# core_module.net
KiCad netlist of a schematic drawn in Altium Designer
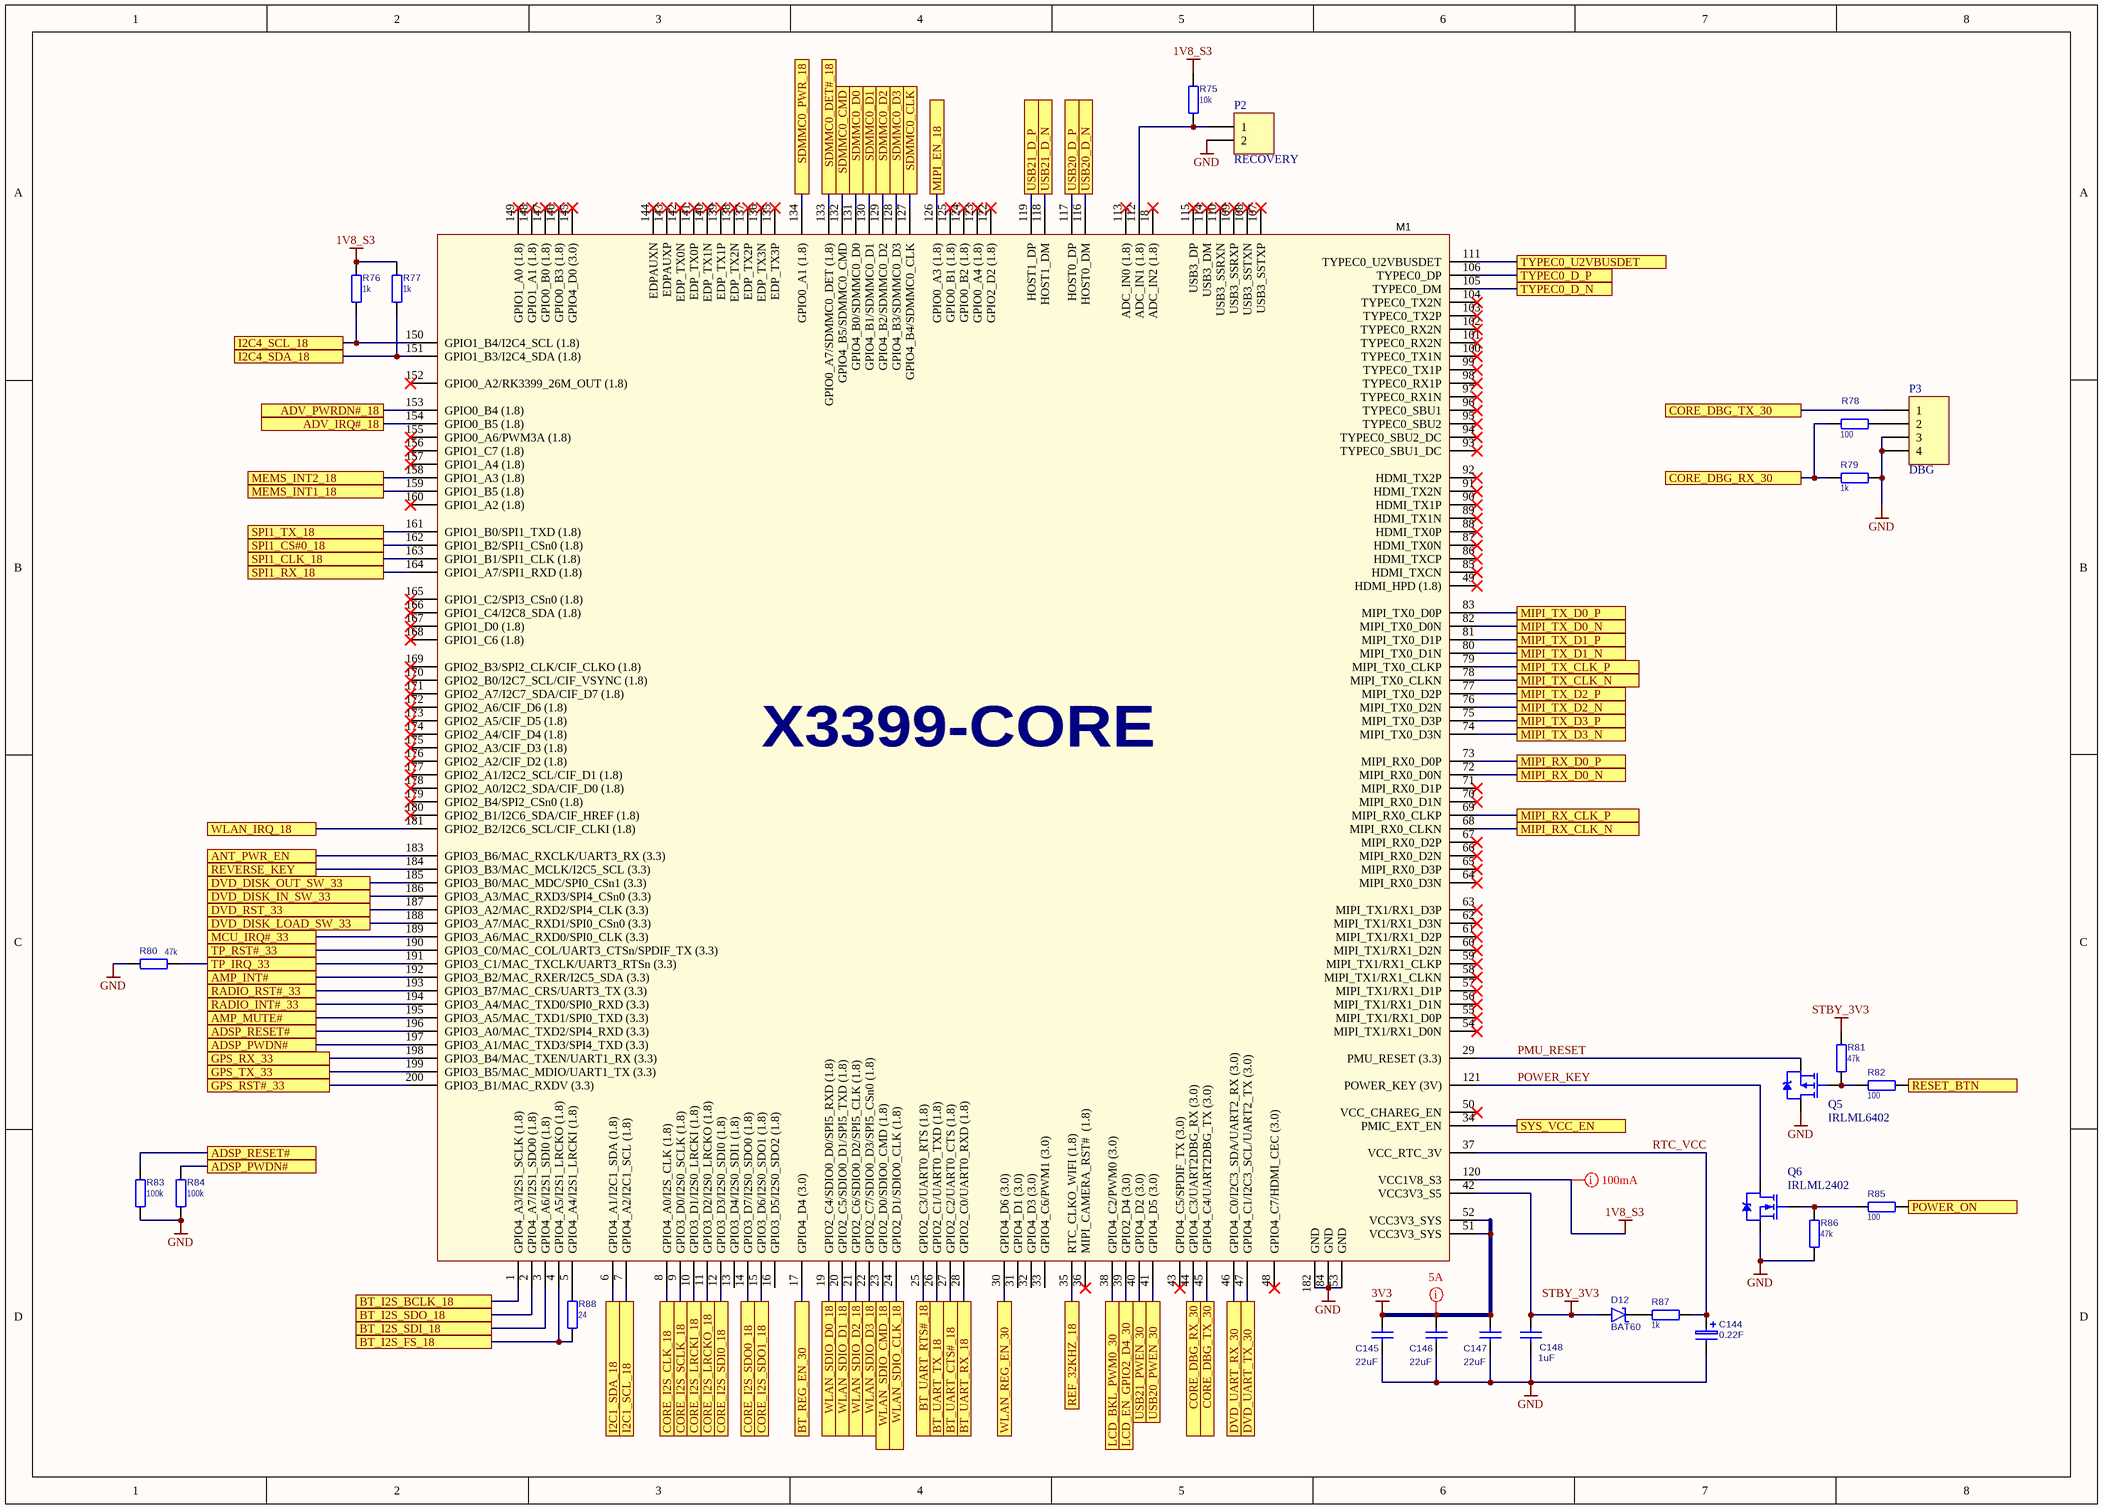
[diagram p0: core_module.SchDoc]

(export (version "E")
  (design (tool "Eeschema 10.0.6"))
  (components
    (comp (ref "C144")
      (value "0.22F")
      (footprint "Capacitors:DS/DSK")
      (description "CAP_POL")
      (libsource (lib "capacitors") (part "CAP_POL"))
    )
    (comp (ref "C145")
      (value "22uF")
      (footprint "Capacitors:C0805")
      (description "CAP_NPOL")
      (fields (field (name "Comment") "CL21A226MQQNNNE"))
      (libsource (lib "capacitors") (part "CAP_NPOL"))
    )
    (comp (ref "C146")
      (value "22uF")
      (footprint "Capacitors:C0805")
      (description "CAP_NPOL")
      (fields (field (name "Comment") "CL21A226MQQNNNE"))
      (libsource (lib "capacitors") (part "CAP_NPOL"))
    )
    (comp (ref "C147")
      (value "22uF")
      (footprint "Capacitors:C0805")
      (description "CAP_NPOL")
      (fields (field (name "Comment") "CL21A226MQQNNNE"))
      (libsource (lib "capacitors") (part "CAP_NPOL"))
    )
    (comp (ref "C148")
      (value "1uF")
      (footprint "Capacitors:C0603")
      (description "CAP_NPOL")
      (fields (field (name "Comment") "CC0603KRX7R9BB105"))
      (libsource (lib "capacitors") (part "CAP_NPOL"))
    )
    (comp (ref "D12")
      (value "BAT60")
      (footprint "SOD-323")
      (description "SHOTTKY")
      (fields (field (name "Comment") "BAT60AE6327HTSA1"))
      (libsource (lib "diodes") (part "SHOTTKY"))
    )
    (comp (ref "M1")
      (value "X3399-CORE")
      (footprint "X3399-CORE")
      (description "RK3399 Six-Core 64-bit")
      (libsource (lib "X3399-CORE") (part "X3399-CORE"))
    )
    (comp (ref "P2")
      (value "RECOVERY")
      (footprint "HDR:PLS-2")
      (description "Header, 2-Pin")
      (fields (field (name "PUBLISHER") "Altium Limited"))
      (libsource (lib "HDR") (part "HDR 2"))
    )
    (comp (ref "P3")
      (value "DBG")
      (footprint "PLD-2")
      (description "Header, 4-Pin")
      (fields (field (name "PUBLISHER") "Altium Limited"))
      (libsource (lib "HDR") (part "HDR 4"))
    )
    (comp (ref "Q5")
      (value "IRLML6402")
      (footprint "SOT:SOT-23-3")
      (description "HEXFET Power MOSFET")
      (libsource (lib "MOSFET") (part "P-Channel"))
    )
    (comp (ref "Q6")
      (value "IRLML2402")
      (footprint "SOT:SOT-23-3")
      (description "HEXFET Power MOSFET")
      (libsource (lib "MOSFET") (part "N-Channel"))
    )
    (comp (ref "R75")
      (value "10k")
      (footprint "R0603")
      (description "RES")
      (libsource (lib "resistors") (part "RESISTOR"))
    )
    (comp (ref "R76")
      (value "1k")
      (footprint "R0603")
      (description "RES")
      (libsource (lib "resistors") (part "RESISTOR"))
    )
    (comp (ref "R77")
      (value "1k")
      (footprint "R0603")
      (description "RES")
      (libsource (lib "resistors") (part "RESISTOR"))
    )
    (comp (ref "R78")
      (value "100")
      (footprint "R0603")
      (description "RES")
      (libsource (lib "resistors") (part "RESISTOR"))
    )
    (comp (ref "R79")
      (value "1k")
      (footprint "R0603")
      (description "RES")
      (libsource (lib "resistors") (part "RESISTOR"))
    )
    (comp (ref "R80")
      (value "47k")
      (footprint "R0603")
      (description "RES")
      (libsource (lib "resistors") (part "RESISTOR"))
    )
    (comp (ref "R81")
      (value "47k")
      (footprint "R0603")
      (description "RES")
      (libsource (lib "resistors") (part "RESISTOR"))
    )
    (comp (ref "R82")
      (value "100")
      (footprint "R0603")
      (description "RES")
      (libsource (lib "resistors") (part "RESISTOR"))
    )
    (comp (ref "R83")
      (value "100k")
      (footprint "R0603")
      (description "RES")
      (libsource (lib "resistors") (part "RESISTOR"))
    )
    (comp (ref "R84")
      (value "100k")
      (footprint "R0603")
      (description "RES")
      (libsource (lib "resistors") (part "RESISTOR"))
    )
    (comp (ref "R85")
      (value "100")
      (footprint "R0603")
      (description "RES")
      (libsource (lib "resistors") (part "RESISTOR"))
    )
    (comp (ref "R86")
      (value "47k")
      (footprint "R0603")
      (description "RES")
      (libsource (lib "resistors") (part "RESISTOR"))
    )
    (comp (ref "R87")
      (value "1k")
      (footprint "R0603")
      (description "RES")
      (libsource (lib "resistors") (part "RESISTOR"))
    )
    (comp (ref "R88")
      (value "24")
      (footprint "R0603")
      (description "RES")
      (libsource (lib "resistors") (part "RESISTOR"))
    )
  )
  (nets
    (net (code "1") (name "/ADSP_PWDN#") (class "Default")
      (node (ref "M1") (pin "197") (pinfunction "GPIO3_A1/MAC_TXD3/SPI4_TXD_(3.3)_197") (pintype "passive"))
      (node (ref "R84") (pin "1") (pinfunction "1_1") (pintype "passive"))
    )
    (net (code "2") (name "/ADSP_RESET#") (class "Default")
      (node (ref "M1") (pin "196") (pinfunction "GPIO3_A0/MAC_TXD2/SPI4_RXD_(3.3)_196") (pintype "passive"))
      (node (ref "R83") (pin "1") (pinfunction "1_1") (pintype "passive"))
    )
    (net (code "3") (name "/ADV_IRQ#_18") (class "Default")
      (node (ref "M1") (pin "154") (pinfunction "GPIO0_B5_(1.8)_154") (pintype "passive"))
    )
    (net (code "4") (name "/ADV_PWRDN#_18") (class "Default")
      (node (ref "M1") (pin "153") (pinfunction "GPIO0_B4_(1.8)_153") (pintype "passive"))
    )
    (net (code "5") (name "/AMP_INT#") (class "Default")
      (node (ref "M1") (pin "192") (pinfunction "GPIO3_B2/MAC_RXER/I2C5_SDA_(3.3)_192") (pintype "passive"))
    )
    (net (code "6") (name "/AMP_MUTE#") (class "Default")
      (node (ref "M1") (pin "195") (pinfunction "GPIO3_A5/MAC_TXD1/SPI0_TXD_(3.3)_195") (pintype "passive"))
    )
    (net (code "7") (name "/ANT_PWR_EN") (class "Default")
      (node (ref "M1") (pin "183") (pinfunction "GPIO3_B6/MAC_RXCLK/UART3_RX_(3.3)_183") (pintype "passive"))
    )
    (net (code "8") (name "/BT_I2S_BCLK_18") (class "Default")
      (node (ref "M1") (pin "1") (pinfunction "GPIO4_A3/I2S1_SCLK_(1.8)_1") (pintype "passive"))
    )
    (net (code "9") (name "/BT_I2S_FS_18") (class "Default")
      (node (ref "M1") (pin "4") (pinfunction "GPIO4_A5/I2S1_LRCKO_(1.8)_4") (pintype "passive"))
      (node (ref "R88") (pin "2") (pinfunction "2_2") (pintype "passive"))
    )
    (net (code "10") (name "/BT_I2S_SDI_18") (class "Default")
      (node (ref "M1") (pin "3") (pinfunction "GPIO4_A6/I2S1_SDI0_(1.8)_3") (pintype "passive"))
    )
    (net (code "11") (name "/BT_I2S_SDO_18") (class "Default")
      (node (ref "M1") (pin "2") (pinfunction "GPIO4_A7/I2S1_SDO0_(1.8)_2") (pintype "passive"))
    )
    (net (code "12") (name "/BT_REG_EN_30") (class "Default")
      (node (ref "M1") (pin "17") (pinfunction "GPIO4_D4_(3.0)_17") (pintype "passive"))
    )
    (net (code "13") (name "/BT_UART_CTS#_18") (class "Default")
      (node (ref "M1") (pin "27") (pinfunction "GPIO2_C2/UART0_CTS_(1.8)_27") (pintype "passive"))
    )
    (net (code "14") (name "/BT_UART_RTS#_18") (class "Default")
      (node (ref "M1") (pin "25") (pinfunction "GPIO2_C3/UART0_RTS_(1.8)_25") (pintype "passive"))
    )
    (net (code "15") (name "/BT_UART_RX_18") (class "Default")
      (node (ref "M1") (pin "28") (pinfunction "GPIO2_C0/UART0_RXD_(1.8)_28") (pintype "passive"))
    )
    (net (code "16") (name "/BT_UART_TX_18") (class "Default")
      (node (ref "M1") (pin "26") (pinfunction "GPIO2_C1/UART0_TXD_(1.8)_26") (pintype "passive"))
    )
    (net (code "17") (name "/CORE_DBG_RX_30") (class "Default")
      (node (ref "M1") (pin "44") (pinfunction "GPIO4_C3/UART2DBG_RX_(3.0)_44") (pintype "passive"))
      (node (ref "R78") (pin "2") (pinfunction "2_2") (pintype "passive"))
      (node (ref "R79") (pin "1") (pinfunction "1_1") (pintype "passive"))
    )
    (net (code "18") (name "/CORE_DBG_TX_30") (class "Default")
      (node (ref "M1") (pin "45") (pinfunction "GPIO4_C4/UART2DBG_TX_(3.0)_45") (pintype "passive"))
      (node (ref "P3") (pin "1") (pinfunction "1_1") (pintype "passive"))
    )
    (net (code "19") (name "/CORE_I2S_CLK_18") (class "Default")
      (node (ref "M1") (pin "8") (pinfunction "GPIO4_A0/I2S_CLK_(1.8)_8") (pintype "passive"))
    )
    (net (code "20") (name "/CORE_I2S_LRCKI_18") (class "Default")
      (node (ref "M1") (pin "10") (pinfunction "GPIO3_D1/I2S0_LRCKI_(1.8)_10") (pintype "passive"))
    )
    (net (code "21") (name "/CORE_I2S_LRCKO_18") (class "Default")
      (node (ref "M1") (pin "11") (pinfunction "GPIO3_D2/I2S0_LRCKO_(1.8)_11") (pintype "passive"))
    )
    (net (code "22") (name "/CORE_I2S_SCLK_18") (class "Default")
      (node (ref "M1") (pin "9") (pinfunction "GPIO3_D0/I2S0_SCLK_(1.8)_9") (pintype "passive"))
    )
    (net (code "23") (name "/CORE_I2S_SDI0_18") (class "Default")
      (node (ref "M1") (pin "12") (pinfunction "GPIO3_D3/I2S0_SDI0_(1.8)_12") (pintype "passive"))
    )
    (net (code "24") (name "/CORE_I2S_SDO0_18") (class "Default")
      (node (ref "M1") (pin "14") (pinfunction "GPIO3_D7/I2S0_SDO0_(1.8)_14") (pintype "passive"))
    )
    (net (code "25") (name "/CORE_I2S_SDO1_18") (class "Default")
      (node (ref "M1") (pin "15") (pinfunction "GPIO3_D6/I2S0_SDO1_(1.8)_15") (pintype "passive"))
    )
    (net (code "26") (name "/DVD_DISK_IN_SW_33") (class "Default")
      (node (ref "M1") (pin "186") (pinfunction "GPIO3_A3/MAC_RXD3/SPI4_CSn0_(3.3)_186") (pintype "passive"))
    )
    (net (code "27") (name "/DVD_DISK_LOAD_SW_33") (class "Default")
      (node (ref "M1") (pin "188") (pinfunction "GPIO3_A7/MAC_RXD1/SPI0_CSn0_(3.3)_188") (pintype "passive"))
    )
    (net (code "28") (name "/DVD_DISK_OUT_SW_33") (class "Default")
      (node (ref "M1") (pin "185") (pinfunction "GPIO3_B0/MAC_MDC/SPI0_CSn1_(3.3)_185") (pintype "passive"))
    )
    (net (code "29") (name "/DVD_RST_33") (class "Default")
      (node (ref "M1") (pin "187") (pinfunction "GPIO3_A2/MAC_RXD2/SPI4_CLK_(3.3)_187") (pintype "passive"))
    )
    (net (code "30") (name "/DVD_UART_RX_30") (class "Default")
      (node (ref "M1") (pin "46") (pinfunction "GPIO4_C0/I2C3_SDA/UART2_RX_(3.0)_46") (pintype "passive"))
    )
    (net (code "31") (name "/DVD_UART_TX_30") (class "Default")
      (node (ref "M1") (pin "47") (pinfunction "GPIO4_C1/I2C3_SCL/UART2_TX_(3.0)_47") (pintype "passive"))
    )
    (net (code "32") (name "/GPS_RST#_33") (class "Default")
      (node (ref "M1") (pin "200") (pinfunction "GPIO3_B1/MAC_RXDV_(3.3)_200") (pintype "passive"))
    )
    (net (code "33") (name "/GPS_RX_33") (class "Default")
      (node (ref "M1") (pin "198") (pinfunction "GPIO3_B4/MAC_TXEN/UART1_RX_(3.3)_198") (pintype "passive"))
    )
    (net (code "34") (name "/GPS_TX_33") (class "Default")
      (node (ref "M1") (pin "199") (pinfunction "GPIO3_B5/MAC_MDIO/UART1_TX_(3.3)_199") (pintype "passive"))
    )
    (net (code "35") (name "/I2C1_SCL_18") (class "Default")
      (node (ref "M1") (pin "7") (pinfunction "GPIO4_A2/I2C1_SCL_(1.8)_7") (pintype "passive"))
    )
    (net (code "36") (name "/I2C1_SDA_18") (class "Default")
      (node (ref "M1") (pin "6") (pinfunction "GPIO4_A1/I2C1_SDA_(1.8)_6") (pintype "passive"))
    )
    (net (code "37") (name "/I2C4_SCL_18") (class "Default")
      (node (ref "M1") (pin "150") (pinfunction "GPIO1_B4/I2C4_SCL_(1.8)_150") (pintype "passive"))
      (node (ref "R76") (pin "1") (pinfunction "1_1") (pintype "passive"))
    )
    (net (code "38") (name "/I2C4_SDA_18") (class "Default")
      (node (ref "M1") (pin "151") (pinfunction "GPIO1_B3/I2C4_SDA_(1.8)_151") (pintype "passive"))
      (node (ref "R77") (pin "2") (pinfunction "2_2") (pintype "passive"))
    )
    (net (code "39") (name "/LCD_BKL_PWM0_30") (class "Default")
      (node (ref "M1") (pin "38") (pinfunction "GPIO4_C2/PWM0_(3.0)_38") (pintype "passive"))
    )
    (net (code "40") (name "/LCD_EN_GPIO2_D4_30") (class "Default")
      (node (ref "M1") (pin "39") (pinfunction "GPIO2_D4_(3.0)_39") (pintype "passive"))
    )
    (net (code "41") (name "/MCU_IRQ#_33") (class "Default")
      (node (ref "M1") (pin "189") (pinfunction "GPIO3_A6/MAC_RXD0/SPI0_CLK_(3.3)_189") (pintype "passive"))
    )
    (net (code "42") (name "/MEMS_INT1_18") (class "Default")
      (node (ref "M1") (pin "159") (pinfunction "GPIO1_B5_(1.8)_159") (pintype "passive"))
    )
    (net (code "43") (name "/MEMS_INT2_18") (class "Default")
      (node (ref "M1") (pin "158") (pinfunction "GPIO1_A3_(1.8)_158") (pintype "passive"))
    )
    (net (code "44") (name "/MIPI_EN_18") (class "Default")
      (node (ref "M1") (pin "126") (pinfunction "GPIO0_A3_(1.8)_126") (pintype "passive"))
    )
    (net (code "45") (name "/MIPI_RX_CLK_N") (class "Default")
      (node (ref "M1") (pin "68") (pinfunction "MIPI_RX0_CLKN_68") (pintype "passive"))
    )
    (net (code "46") (name "/MIPI_RX_CLK_P") (class "Default")
      (node (ref "M1") (pin "69") (pinfunction "MIPI_RX0_CLKP_69") (pintype "passive"))
    )
    (net (code "47") (name "/MIPI_RX_D0_N") (class "Default")
      (node (ref "M1") (pin "72") (pinfunction "MIPI_RX0_D0N_72") (pintype "passive"))
    )
    (net (code "48") (name "/MIPI_RX_D0_P") (class "Default")
      (node (ref "M1") (pin "73") (pinfunction "MIPI_RX0_D0P_73") (pintype "passive"))
    )
    (net (code "49") (name "/MIPI_TX_CLK_N") (class "Default")
      (node (ref "M1") (pin "78") (pinfunction "MIPI_TX0_CLKN_78") (pintype "passive"))
    )
    (net (code "50") (name "/MIPI_TX_CLK_P") (class "Default")
      (node (ref "M1") (pin "79") (pinfunction "MIPI_TX0_CLKP_79") (pintype "passive"))
    )
    (net (code "51") (name "/MIPI_TX_D0_N") (class "Default")
      (node (ref "M1") (pin "82") (pinfunction "MIPI_TX0_D0N_82") (pintype "passive"))
    )
    (net (code "52") (name "/MIPI_TX_D0_P") (class "Default")
      (node (ref "M1") (pin "83") (pinfunction "MIPI_TX0_D0P_83") (pintype "passive"))
    )
    (net (code "53") (name "/MIPI_TX_D1_N") (class "Default")
      (node (ref "M1") (pin "80") (pinfunction "MIPI_TX0_D1N_80") (pintype "passive"))
    )
    (net (code "54") (name "/MIPI_TX_D1_P") (class "Default")
      (node (ref "M1") (pin "81") (pinfunction "MIPI_TX0_D1P_81") (pintype "passive"))
    )
    (net (code "55") (name "/MIPI_TX_D2_N") (class "Default")
      (node (ref "M1") (pin "76") (pinfunction "MIPI_TX0_D2N_76") (pintype "passive"))
    )
    (net (code "56") (name "/MIPI_TX_D2_P") (class "Default")
      (node (ref "M1") (pin "77") (pinfunction "MIPI_TX0_D2P_77") (pintype "passive"))
    )
    (net (code "57") (name "/MIPI_TX_D3_N") (class "Default")
      (node (ref "M1") (pin "74") (pinfunction "MIPI_TX0_D3N_74") (pintype "passive"))
    )
    (net (code "58") (name "/MIPI_TX_D3_P") (class "Default")
      (node (ref "M1") (pin "75") (pinfunction "MIPI_TX0_D3P_75") (pintype "passive"))
    )
    (net (code "59") (name "/PMU_RESET") (class "Default")
      (node (ref "M1") (pin "29") (pinfunction "PMU_RESET_(3.3)_29") (pintype "passive"))
      (node (ref "Q5") (pin "2") (pinfunction "S_2") (pintype "passive"))
    )
    (net (code "60") (name "/POWER_KEY") (class "Default")
      (node (ref "M1") (pin "121") (pinfunction "POWER_KEY_(3V)_121") (pintype "passive"))
      (node (ref "Q6") (pin "3") (pinfunction "D_3") (pintype "passive"))
    )
    (net (code "61") (name "/POWER_ON") (class "Default")
      (node (ref "R85") (pin "1") (pinfunction "1_1") (pintype "passive"))
    )
    (net (code "62") (name "/RADIO_INT#_33") (class "Default")
      (node (ref "M1") (pin "194") (pinfunction "GPIO3_A4/MAC_TXD0/SPI0_RXD_(3.3)_194") (pintype "passive"))
    )
    (net (code "63") (name "/RADIO_RST#_33") (class "Default")
      (node (ref "M1") (pin "193") (pinfunction "GPIO3_B7/MAC_CRS/UART3_TX_(3.3)_193") (pintype "passive"))
    )
    (net (code "64") (name "/REF_32KHZ_18") (class "Default")
      (node (ref "M1") (pin "35") (pinfunction "RTC_CLKO_WIFI_(1.8)_35") (pintype "passive"))
    )
    (net (code "65") (name "/RESET_BTN") (class "Default")
      (node (ref "R82") (pin "1") (pinfunction "1_1") (pintype "passive"))
    )
    (net (code "66") (name "/REVERSE_KEY") (class "Default")
      (node (ref "M1") (pin "184") (pinfunction "GPIO3_B3/MAC_MCLK/I2C5_SCL_(3.3)_184") (pintype "passive"))
    )
    (net (code "67") (name "/RTC_VCC") (class "Default")
      (node (ref "C144") (pin "1") (pinfunction "+_1") (pintype "passive"))
      (node (ref "M1") (pin "37") (pinfunction "VCC_RTC_3V_37") (pintype "passive"))
      (node (ref "R87") (pin "1") (pinfunction "1_1") (pintype "passive"))
    )
    (net (code "68") (name "/SDMMC0_CLK") (class "Default")
      (node (ref "M1") (pin "127") (pinfunction "GPIO4_B4/SDMMC0_CLK_127") (pintype "passive"))
    )
    (net (code "69") (name "/SDMMC0_CMD") (class "Default")
      (node (ref "M1") (pin "132") (pinfunction "GPIO4_B5/SDMMC0_CMD_132") (pintype "passive"))
    )
    (net (code "70") (name "/SDMMC0_D0") (class "Default")
      (node (ref "M1") (pin "131") (pinfunction "GPIO4_B0/SDMMC0_D0_131") (pintype "passive"))
    )
    (net (code "71") (name "/SDMMC0_D1") (class "Default")
      (node (ref "M1") (pin "130") (pinfunction "GPIO4_B1/SDMMC0_D1_130") (pintype "passive"))
    )
    (net (code "72") (name "/SDMMC0_D2") (class "Default")
      (node (ref "M1") (pin "129") (pinfunction "GPIO4_B2/SDMMC0_D2_129") (pintype "passive"))
    )
    (net (code "73") (name "/SDMMC0_D3") (class "Default")
      (node (ref "M1") (pin "128") (pinfunction "GPIO4_B3/SDMMC0_D3_128") (pintype "passive"))
    )
    (net (code "74") (name "/SDMMC0_DET#_18") (class "Default")
      (node (ref "M1") (pin "133") (pinfunction "GPIO0_A7/SDMMC0_DET_(1.8)_133") (pintype "passive"))
    )
    (net (code "75") (name "/SDMMC0_PWR_18") (class "Default")
      (node (ref "M1") (pin "134") (pinfunction "GPIO0_A1_(1.8)_134") (pintype "passive"))
    )
    (net (code "76") (name "/SPI1_CLK_18") (class "Default")
      (node (ref "M1") (pin "163") (pinfunction "GPIO1_B1/SPI1_CLK_(1.8)_163") (pintype "passive"))
    )
    (net (code "77") (name "/SPI1_CS#0_18") (class "Default")
      (node (ref "M1") (pin "162") (pinfunction "GPIO1_B2/SPI1_CSn0_(1.8)_162") (pintype "passive"))
    )
    (net (code "78") (name "/SPI1_RX_18") (class "Default")
      (node (ref "M1") (pin "164") (pinfunction "GPIO1_A7/SPI1_RXD_(1.8)_164") (pintype "passive"))
    )
    (net (code "79") (name "/SPI1_TX_18") (class "Default")
      (node (ref "M1") (pin "161") (pinfunction "GPIO1_B0/SPI1_TXD_(1.8)_161") (pintype "passive"))
    )
    (net (code "80") (name "/SYS_VCC_EN") (class "Default")
      (node (ref "M1") (pin "34") (pinfunction "PMIC_EXT_EN_34") (pintype "passive"))
    )
    (net (code "81") (name "/TP_IRQ_33") (class "Default")
      (node (ref "M1") (pin "191") (pinfunction "GPIO3_C1/MAC_TXCLK/UART3_RTSn_(3.3)_191") (pintype "passive"))
      (node (ref "R80") (pin "2") (pinfunction "2_2") (pintype "passive"))
    )
    (net (code "82") (name "/TP_RST#_33") (class "Default")
      (node (ref "M1") (pin "190") (pinfunction "GPIO3_C0/MAC_COL/UART3_CTSn/SPDIF_TX_(3.3)_190") (pintype "passive"))
    )
    (net (code "83") (name "/TYPEC0_D_N") (class "Default")
      (node (ref "M1") (pin "105") (pinfunction "TYPEC0_DM_105") (pintype "passive"))
    )
    (net (code "84") (name "/TYPEC0_D_P") (class "Default")
      (node (ref "M1") (pin "106") (pinfunction "TYPEC0_DP_106") (pintype "passive"))
    )
    (net (code "85") (name "/TYPEC0_U2VBUSDET") (class "Default")
      (node (ref "M1") (pin "111") (pinfunction "TYPEC0_U2VBUSDET_111") (pintype "passive"))
    )
    (net (code "86") (name "/USB20_D_N") (class "Default")
      (node (ref "M1") (pin "116") (pinfunction "HOST0_DM_116") (pintype "passive"))
    )
    (net (code "87") (name "/USB20_D_P") (class "Default")
      (node (ref "M1") (pin "117") (pinfunction "HOST0_DP_117") (pintype "passive"))
    )
    (net (code "88") (name "/USB20_PWEN_30") (class "Default")
      (node (ref "M1") (pin "41") (pinfunction "GPIO4_D5_(3.0)_41") (pintype "passive"))
    )
    (net (code "89") (name "/USB21_D_N") (class "Default")
      (node (ref "M1") (pin "118") (pinfunction "HOST1_DM_118") (pintype "passive"))
    )
    (net (code "90") (name "/USB21_D_P") (class "Default")
      (node (ref "M1") (pin "119") (pinfunction "HOST1_DP_119") (pintype "passive"))
    )
    (net (code "91") (name "/USB21_PWEN_30") (class "Default")
      (node (ref "M1") (pin "40") (pinfunction "GPIO4_D2_(3.0)_40") (pintype "passive"))
    )
    (net (code "92") (name "/WLAN_IRQ_18") (class "Default")
      (node (ref "M1") (pin "181") (pinfunction "GPIO2_B2/I2C6_SCL/CIF_CLKI_(1.8)_181") (pintype "passive"))
    )
    (net (code "93") (name "/WLAN_REG_EN_30") (class "Default")
      (node (ref "M1") (pin "30") (pinfunction "GPIO4_D6_(3.0)_30") (pintype "passive"))
    )
    (net (code "94") (name "/WLAN_SDIO_CLK_18") (class "Default")
      (node (ref "M1") (pin "24") (pinfunction "GPIO2_D1/SDIO0_CLK_(1.8)_24") (pintype "passive"))
    )
    (net (code "95") (name "/WLAN_SDIO_CMD_18") (class "Default")
      (node (ref "M1") (pin "23") (pinfunction "GPIO2_D0/SDIO0_CMD_(1.8)_23") (pintype "passive"))
    )
    (net (code "96") (name "/WLAN_SDIO_D0_18") (class "Default")
      (node (ref "M1") (pin "19") (pinfunction "GPIO2_C4/SDIO0_D0/SPI5_RXD_(1.8)_19") (pintype "passive"))
    )
    (net (code "97") (name "/WLAN_SDIO_D1_18") (class "Default")
      (node (ref "M1") (pin "20") (pinfunction "GPIO2_C5/SDIO0_D1/SPI5_TXD_(1.8)_20") (pintype "passive"))
    )
    (net (code "98") (name "/WLAN_SDIO_D2_18") (class "Default")
      (node (ref "M1") (pin "21") (pinfunction "GPIO2_C6/SDIO0_D2/SPI5_CLK_(1.8)_21") (pintype "passive"))
    )
    (net (code "99") (name "/WLAN_SDIO_D3_18") (class "Default")
      (node (ref "M1") (pin "22") (pinfunction "GPIO2_C7/SDIO0_D3/SPI5_CSn0_(1.8)_22") (pintype "passive"))
    )
    (net (code "100") (name "1V8_S3") (class "Default")
      (node (ref "M1") (pin "120") (pinfunction "VCC1V8_S3_120") (pintype "passive"))
      (node (ref "R75") (pin "2") (pinfunction "2_2") (pintype "passive"))
      (node (ref "R76") (pin "2") (pinfunction "2_2") (pintype "passive"))
      (node (ref "R77") (pin "1") (pinfunction "1_1") (pintype "passive"))
    )
    (net (code "101") (name "3V3") (class "Default")
      (node (ref "C145") (pin "1") (pinfunction "1_1") (pintype "passive"))
      (node (ref "C146") (pin "1") (pinfunction "1_1") (pintype "passive"))
      (node (ref "C147") (pin "1") (pinfunction "1_1") (pintype "passive"))
      (node (ref "M1") (pin "51") (pinfunction "VCC3V3_SYS_51") (pintype "passive"))
      (node (ref "M1") (pin "52") (pinfunction "VCC3V3_SYS_52") (pintype "passive"))
    )
    (net (code "102") (name "GND") (class "Default")
      (node (ref "C144") (pin "2") (pinfunction "-_2") (pintype "passive"))
      (node (ref "C145") (pin "2") (pinfunction "2_2") (pintype "passive"))
      (node (ref "C146") (pin "2") (pinfunction "2_2") (pintype "passive"))
      (node (ref "C147") (pin "2") (pinfunction "2_2") (pintype "passive"))
      (node (ref "C148") (pin "1") (pinfunction "1_1") (pintype "passive"))
      (node (ref "M1") (pin "182") (pinfunction "GND_182") (pintype "passive"))
      (node (ref "M1") (pin "53") (pinfunction "GND_53") (pintype "passive"))
      (node (ref "M1") (pin "84") (pinfunction "GND_84") (pintype "passive"))
      (node (ref "P2") (pin "2") (pinfunction "2_2") (pintype "passive"))
      (node (ref "P3") (pin "3") (pinfunction "3_3") (pintype "passive"))
      (node (ref "P3") (pin "4") (pinfunction "4_4") (pintype "passive"))
      (node (ref "Q5") (pin "3") (pinfunction "D_3") (pintype "passive"))
      (node (ref "Q6") (pin "2") (pinfunction "S_2") (pintype "passive"))
      (node (ref "R79") (pin "2") (pinfunction "2_2") (pintype "passive"))
      (node (ref "R80") (pin "1") (pinfunction "1_1") (pintype "passive"))
      (node (ref "R83") (pin "2") (pinfunction "2_2") (pintype "passive"))
      (node (ref "R84") (pin "2") (pinfunction "2_2") (pintype "passive"))
      (node (ref "R86") (pin "2") (pinfunction "2_2") (pintype "passive"))
    )
    (net (code "103") (name "Net-(D12-K)") (class "Default")
      (node (ref "D12") (pin "2") (pinfunction "K_2") (pintype "passive"))
      (node (ref "R87") (pin "2") (pinfunction "2_2") (pintype "passive"))
    )
    (net (code "104") (name "Net-(M1-ADC_IN1_(1.8))") (class "Default")
      (node (ref "M1") (pin "112") (pinfunction "ADC_IN1_(1.8)_112") (pintype "passive"))
      (node (ref "P2") (pin "1") (pinfunction "1_1") (pintype "passive"))
      (node (ref "R75") (pin "1") (pinfunction "1_1") (pintype "passive"))
    )
    (net (code "105") (name "Net-(M1-GPIO4_A4{slash}I2S1_LRCKI_(1.8))") (class "Default")
      (node (ref "M1") (pin "5") (pinfunction "GPIO4_A4/I2S1_LRCKI_(1.8)_5") (pintype "passive"))
      (node (ref "R88") (pin "1") (pinfunction "1_1") (pintype "passive"))
    )
    (net (code "106") (name "Net-(P3-Pad2)") (class "Default")
      (node (ref "P3") (pin "2") (pinfunction "2_2") (pintype "passive"))
      (node (ref "R78") (pin "1") (pinfunction "1_1") (pintype "passive"))
    )
    (net (code "107") (name "Net-(Q5-G)") (class "Default")
      (node (ref "Q5") (pin "1") (pinfunction "G_1") (pintype "passive"))
      (node (ref "R81") (pin "2") (pinfunction "2_2") (pintype "passive"))
      (node (ref "R82") (pin "2") (pinfunction "2_2") (pintype "passive"))
    )
    (net (code "108") (name "Net-(Q6-G)") (class "Default")
      (node (ref "Q6") (pin "1") (pinfunction "G_1") (pintype "passive"))
      (node (ref "R85") (pin "2") (pinfunction "2_2") (pintype "passive"))
      (node (ref "R86") (pin "1") (pinfunction "1_1") (pintype "passive"))
    )
    (net (code "109") (name "STBY_3V3") (class "Default")
      (node (ref "C148") (pin "2") (pinfunction "2_2") (pintype "passive"))
      (node (ref "D12") (pin "1") (pinfunction "A_1") (pintype "passive"))
      (node (ref "M1") (pin "42") (pinfunction "VCC3V3_S5_42") (pintype "passive"))
      (node (ref "R81") (pin "1") (pinfunction "1_1") (pintype "passive"))
    )
    (net (code "110") (name "unconnected-(M1-ADC_IN0_(1.8)-Pad113)") (class "Default")
      (node (ref "M1") (pin "113") (pinfunction "ADC_IN0_(1.8)_113") (pintype "passive+no_connect"))
    )
    (net (code "111") (name "unconnected-(M1-ADC_IN2_(1.8)-Pad18)") (class "Default")
      (node (ref "M1") (pin "18") (pinfunction "ADC_IN2_(1.8)_18") (pintype "passive+no_connect"))
    )
    (net (code "112") (name "unconnected-(M1-EDPAUXN-Pad144)") (class "Default")
      (node (ref "M1") (pin "144") (pinfunction "EDPAUXN_144") (pintype "passive+no_connect"))
    )
    (net (code "113") (name "unconnected-(M1-EDPAUXP-Pad143)") (class "Default")
      (node (ref "M1") (pin "143") (pinfunction "EDPAUXP_143") (pintype "passive+no_connect"))
    )
    (net (code "114") (name "unconnected-(M1-EDP_TX0N-Pad142)") (class "Default")
      (node (ref "M1") (pin "142") (pinfunction "EDP_TX0N_142") (pintype "passive+no_connect"))
    )
    (net (code "115") (name "unconnected-(M1-EDP_TX0P-Pad141)") (class "Default")
      (node (ref "M1") (pin "141") (pinfunction "EDP_TX0P_141") (pintype "passive+no_connect"))
    )
    (net (code "116") (name "unconnected-(M1-EDP_TX1N-Pad140)") (class "Default")
      (node (ref "M1") (pin "140") (pinfunction "EDP_TX1N_140") (pintype "passive+no_connect"))
    )
    (net (code "117") (name "unconnected-(M1-EDP_TX1P-Pad139)") (class "Default")
      (node (ref "M1") (pin "139") (pinfunction "EDP_TX1P_139") (pintype "passive+no_connect"))
    )
    (net (code "118") (name "unconnected-(M1-EDP_TX2N-Pad138)") (class "Default")
      (node (ref "M1") (pin "138") (pinfunction "EDP_TX2N_138") (pintype "passive+no_connect"))
    )
    (net (code "119") (name "unconnected-(M1-EDP_TX2P-Pad137)") (class "Default")
      (node (ref "M1") (pin "137") (pinfunction "EDP_TX2P_137") (pintype "passive+no_connect"))
    )
    (net (code "120") (name "unconnected-(M1-EDP_TX3N-Pad136)") (class "Default")
      (node (ref "M1") (pin "136") (pinfunction "EDP_TX3N_136") (pintype "passive+no_connect"))
    )
    (net (code "121") (name "unconnected-(M1-EDP_TX3P-Pad135)") (class "Default")
      (node (ref "M1") (pin "135") (pinfunction "EDP_TX3P_135") (pintype "passive+no_connect"))
    )
    (net (code "122") (name "unconnected-(M1-GPIO0_A2{slash}RK3399_26M_OUT_(1.8)-Pad152)") (class "Default")
      (node (ref "M1") (pin "152") (pinfunction "GPIO0_A2/RK3399_26M_OUT_(1.8)_152") (pintype "passive+no_connect"))
    )
    (net (code "123") (name "unconnected-(M1-GPIO0_A4_(1.8)-Pad123)") (class "Default")
      (node (ref "M1") (pin "123") (pinfunction "GPIO0_A4_(1.8)_123") (pintype "passive+no_connect"))
    )
    (net (code "124") (name "unconnected-(M1-GPIO0_A6{slash}PWM3A_(1.8)-Pad155)") (class "Default")
      (node (ref "M1") (pin "155") (pinfunction "GPIO0_A6/PWM3A_(1.8)_155") (pintype "passive+no_connect"))
    )
    (net (code "125") (name "unconnected-(M1-GPIO0_B0_(1.8)-Pad147)") (class "Default")
      (node (ref "M1") (pin "147") (pinfunction "GPIO0_B0_(1.8)_147") (pintype "passive+no_connect"))
    )
    (net (code "126") (name "unconnected-(M1-GPIO0_B1_(1.8)-Pad125)") (class "Default")
      (node (ref "M1") (pin "125") (pinfunction "GPIO0_B1_(1.8)_125") (pintype "passive+no_connect"))
    )
    (net (code "127") (name "unconnected-(M1-GPIO0_B2_(1.8)-Pad124)") (class "Default")
      (node (ref "M1") (pin "124") (pinfunction "GPIO0_B2_(1.8)_124") (pintype "passive+no_connect"))
    )
    (net (code "128") (name "unconnected-(M1-GPIO0_B3_(1.8)-Pad146)") (class "Default")
      (node (ref "M1") (pin "146") (pinfunction "GPIO0_B3_(1.8)_146") (pintype "passive+no_connect"))
    )
    (net (code "129") (name "unconnected-(M1-GPIO1_A0_(1.8)-Pad149)") (class "Default")
      (node (ref "M1") (pin "149") (pinfunction "GPIO1_A0_(1.8)_149") (pintype "passive+no_connect"))
    )
    (net (code "130") (name "unconnected-(M1-GPIO1_A1_(1.8)-Pad148)") (class "Default")
      (node (ref "M1") (pin "148") (pinfunction "GPIO1_A1_(1.8)_148") (pintype "passive+no_connect"))
    )
    (net (code "131") (name "unconnected-(M1-GPIO1_A2_(1.8)-Pad160)") (class "Default")
      (node (ref "M1") (pin "160") (pinfunction "GPIO1_A2_(1.8)_160") (pintype "passive+no_connect"))
    )
    (net (code "132") (name "unconnected-(M1-GPIO1_A4_(1.8)-Pad157)") (class "Default")
      (node (ref "M1") (pin "157") (pinfunction "GPIO1_A4_(1.8)_157") (pintype "passive+no_connect"))
    )
    (net (code "133") (name "unconnected-(M1-GPIO1_C2{slash}SPI3_CSn0_(1.8)-Pad165)") (class "Default")
      (node (ref "M1") (pin "165") (pinfunction "GPIO1_C2/SPI3_CSn0_(1.8)_165") (pintype "passive+no_connect"))
    )
    (net (code "134") (name "unconnected-(M1-GPIO1_C4{slash}I2C8_SDA_(1.8)-Pad166)") (class "Default")
      (node (ref "M1") (pin "166") (pinfunction "GPIO1_C4/I2C8_SDA_(1.8)_166") (pintype "passive+no_connect"))
    )
    (net (code "135") (name "unconnected-(M1-GPIO1_C6_(1.8)-Pad168)") (class "Default")
      (node (ref "M1") (pin "168") (pinfunction "GPIO1_C6_(1.8)_168") (pintype "passive+no_connect"))
    )
    (net (code "136") (name "unconnected-(M1-GPIO1_C7_(1.8)-Pad156)") (class "Default")
      (node (ref "M1") (pin "156") (pinfunction "GPIO1_C7_(1.8)_156") (pintype "passive+no_connect"))
    )
    (net (code "137") (name "unconnected-(M1-GPIO1_D0_(1.8)-Pad167)") (class "Default")
      (node (ref "M1") (pin "167") (pinfunction "GPIO1_D0_(1.8)_167") (pintype "passive+no_connect"))
    )
    (net (code "138") (name "unconnected-(M1-GPIO2_A0{slash}I2C2_SDA{slash}CIF_D0_(1.8)-Pad178)") (class "Default")
      (node (ref "M1") (pin "178") (pinfunction "GPIO2_A0/I2C2_SDA/CIF_D0_(1.8)_178") (pintype "passive+no_connect"))
    )
    (net (code "139") (name "unconnected-(M1-GPIO2_A1{slash}I2C2_SCL{slash}CIF_D1_(1.8)-Pad177)") (class "Default")
      (node (ref "M1") (pin "177") (pinfunction "GPIO2_A1/I2C2_SCL/CIF_D1_(1.8)_177") (pintype "passive+no_connect"))
    )
    (net (code "140") (name "unconnected-(M1-GPIO2_A2{slash}CIF_D2_(1.8)-Pad176)") (class "Default")
      (node (ref "M1") (pin "176") (pinfunction "GPIO2_A2/CIF_D2_(1.8)_176") (pintype "passive+no_connect"))
    )
    (net (code "141") (name "unconnected-(M1-GPIO2_A3{slash}CIF_D3_(1.8)-Pad175)") (class "Default")
      (node (ref "M1") (pin "175") (pinfunction "GPIO2_A3/CIF_D3_(1.8)_175") (pintype "passive+no_connect"))
    )
    (net (code "142") (name "unconnected-(M1-GPIO2_A4{slash}CIF_D4_(1.8)-Pad174)") (class "Default")
      (node (ref "M1") (pin "174") (pinfunction "GPIO2_A4/CIF_D4_(1.8)_174") (pintype "passive+no_connect"))
    )
    (net (code "143") (name "unconnected-(M1-GPIO2_A5{slash}CIF_D5_(1.8)-Pad173)") (class "Default")
      (node (ref "M1") (pin "173") (pinfunction "GPIO2_A5/CIF_D5_(1.8)_173") (pintype "passive+no_connect"))
    )
    (net (code "144") (name "unconnected-(M1-GPIO2_A6{slash}CIF_D6_(1.8)-Pad172)") (class "Default")
      (node (ref "M1") (pin "172") (pinfunction "GPIO2_A6/CIF_D6_(1.8)_172") (pintype "passive+no_connect"))
    )
    (net (code "145") (name "unconnected-(M1-GPIO2_A7{slash}I2C7_SDA{slash}CIF_D7_(1.8)-Pad171)") (class "Default")
      (node (ref "M1") (pin "171") (pinfunction "GPIO2_A7/I2C7_SDA/CIF_D7_(1.8)_171") (pintype "passive+no_connect"))
    )
    (net (code "146") (name "unconnected-(M1-GPIO2_B0{slash}I2C7_SCL{slash}CIF_VSYNC_(1.8)-Pad170)") (class "Default")
      (node (ref "M1") (pin "170") (pinfunction "GPIO2_B0/I2C7_SCL/CIF_VSYNC_(1.8)_170") (pintype "passive+no_connect"))
    )
    (net (code "147") (name "unconnected-(M1-GPIO2_B1{slash}I2C6_SDA{slash}CIF_HREF_(1.8)-Pad180)") (class "Default")
      (node (ref "M1") (pin "180") (pinfunction "GPIO2_B1/I2C6_SDA/CIF_HREF_(1.8)_180") (pintype "passive+no_connect"))
    )
    (net (code "148") (name "unconnected-(M1-GPIO2_B3{slash}SPI2_CLK{slash}CIF_CLKO_(1.8)-Pad169)") (class "Default")
      (node (ref "M1") (pin "169") (pinfunction "GPIO2_B3/SPI2_CLK/CIF_CLKO_(1.8)_169") (pintype "passive+no_connect"))
    )
    (net (code "149") (name "unconnected-(M1-GPIO2_B4{slash}SPI2_CSn0_(1.8)-Pad179)") (class "Default")
      (node (ref "M1") (pin "179") (pinfunction "GPIO2_B4/SPI2_CSn0_(1.8)_179") (pintype "passive+no_connect"))
    )
    (net (code "150") (name "unconnected-(M1-GPIO2_D2_(1.8)-Pad122)") (class "Default")
      (node (ref "M1") (pin "122") (pinfunction "GPIO2_D2_(1.8)_122") (pintype "passive+no_connect"))
    )
    (net (code "151") (name "unconnected-(M1-GPIO3_D4{slash}I2S0_SDI1_(1.8)-Pad13)") (class "Default")
      (node (ref "M1") (pin "13") (pinfunction "GPIO3_D4/I2S0_SDI1_(1.8)_13") (pintype "passive"))
    )
    (net (code "152") (name "unconnected-(M1-GPIO3_D5{slash}I2S0_SDO2_(1.8)-Pad16)") (class "Default")
      (node (ref "M1") (pin "16") (pinfunction "GPIO3_D5/I2S0_SDO2_(1.8)_16") (pintype "passive"))
    )
    (net (code "153") (name "unconnected-(M1-GPIO4_C5{slash}SPDIF_TX_(3.0)-Pad43)") (class "Default")
      (node (ref "M1") (pin "43") (pinfunction "GPIO4_C5/SPDIF_TX_(3.0)_43") (pintype "passive+no_connect"))
    )
    (net (code "154") (name "unconnected-(M1-GPIO4_C6{slash}PWM1_(3.0)-Pad33)") (class "Default")
      (node (ref "M1") (pin "33") (pinfunction "GPIO4_C6/PWM1_(3.0)_33") (pintype "passive"))
    )
    (net (code "155") (name "unconnected-(M1-GPIO4_C7{slash}HDMI_CEC_(3.0)-Pad48)") (class "Default")
      (node (ref "M1") (pin "48") (pinfunction "GPIO4_C7/HDMI_CEC_(3.0)_48") (pintype "passive+no_connect"))
    )
    (net (code "156") (name "unconnected-(M1-GPIO4_D0_(3.0)-Pad145)") (class "Default")
      (node (ref "M1") (pin "145") (pinfunction "GPIO4_D0_(3.0)_145") (pintype "passive+no_connect"))
    )
    (net (code "157") (name "unconnected-(M1-GPIO4_D1_(3.0)-Pad31)") (class "Default")
      (node (ref "M1") (pin "31") (pinfunction "GPIO4_D1_(3.0)_31") (pintype "passive"))
    )
    (net (code "158") (name "unconnected-(M1-GPIO4_D3_(3.0)-Pad32)") (class "Default")
      (node (ref "M1") (pin "32") (pinfunction "GPIO4_D3_(3.0)_32") (pintype "passive"))
    )
    (net (code "159") (name "unconnected-(M1-HDMI_HPD_(1.8)-Pad49)") (class "Default")
      (node (ref "M1") (pin "49") (pinfunction "HDMI_HPD_(1.8)_49") (pintype "passive+no_connect"))
    )
    (net (code "160") (name "unconnected-(M1-HDMI_TX0N-Pad87)") (class "Default")
      (node (ref "M1") (pin "87") (pinfunction "HDMI_TX0N_87") (pintype "passive+no_connect"))
    )
    (net (code "161") (name "unconnected-(M1-HDMI_TX0P-Pad88)") (class "Default")
      (node (ref "M1") (pin "88") (pinfunction "HDMI_TX0P_88") (pintype "passive+no_connect"))
    )
    (net (code "162") (name "unconnected-(M1-HDMI_TX1N-Pad89)") (class "Default")
      (node (ref "M1") (pin "89") (pinfunction "HDMI_TX1N_89") (pintype "passive+no_connect"))
    )
    (net (code "163") (name "unconnected-(M1-HDMI_TX1P-Pad90)") (class "Default")
      (node (ref "M1") (pin "90") (pinfunction "HDMI_TX1P_90") (pintype "passive+no_connect"))
    )
    (net (code "164") (name "unconnected-(M1-HDMI_TX2N-Pad91)") (class "Default")
      (node (ref "M1") (pin "91") (pinfunction "HDMI_TX2N_91") (pintype "passive+no_connect"))
    )
    (net (code "165") (name "unconnected-(M1-HDMI_TX2P-Pad92)") (class "Default")
      (node (ref "M1") (pin "92") (pinfunction "HDMI_TX2P_92") (pintype "passive+no_connect"))
    )
    (net (code "166") (name "unconnected-(M1-HDMI_TXCN-Pad85)") (class "Default")
      (node (ref "M1") (pin "85") (pinfunction "HDMI_TXCN_85") (pintype "passive+no_connect"))
    )
    (net (code "167") (name "unconnected-(M1-HDMI_TXCP-Pad86)") (class "Default")
      (node (ref "M1") (pin "86") (pinfunction "HDMI_TXCP_86") (pintype "passive+no_connect"))
    )
    (net (code "168") (name "unconnected-(M1-MIPI_CAMERA_RST#__(1.8)-Pad36)") (class "Default")
      (node (ref "M1") (pin "36") (pinfunction "MIPI_CAMERA_RST#__(1.8)_36") (pintype "passive+no_connect"))
    )
    (net (code "169") (name "unconnected-(M1-MIPI_RX0_D1N-Pad70)") (class "Default")
      (node (ref "M1") (pin "70") (pinfunction "MIPI_RX0_D1N_70") (pintype "passive+no_connect"))
    )
    (net (code "170") (name "unconnected-(M1-MIPI_RX0_D1P-Pad71)") (class "Default")
      (node (ref "M1") (pin "71") (pinfunction "MIPI_RX0_D1P_71") (pintype "passive+no_connect"))
    )
    (net (code "171") (name "unconnected-(M1-MIPI_RX0_D2N-Pad66)") (class "Default")
      (node (ref "M1") (pin "66") (pinfunction "MIPI_RX0_D2N_66") (pintype "passive+no_connect"))
    )
    (net (code "172") (name "unconnected-(M1-MIPI_RX0_D2P-Pad67)") (class "Default")
      (node (ref "M1") (pin "67") (pinfunction "MIPI_RX0_D2P_67") (pintype "passive+no_connect"))
    )
    (net (code "173") (name "unconnected-(M1-MIPI_RX0_D3N-Pad64)") (class "Default")
      (node (ref "M1") (pin "64") (pinfunction "MIPI_RX0_D3N_64") (pintype "passive+no_connect"))
    )
    (net (code "174") (name "unconnected-(M1-MIPI_RX0_D3P-Pad65)") (class "Default")
      (node (ref "M1") (pin "65") (pinfunction "MIPI_RX0_D3P_65") (pintype "passive+no_connect"))
    )
    (net (code "175") (name "unconnected-(M1-MIPI_TX1{slash}RX1_CLKN-Pad58)") (class "Default")
      (node (ref "M1") (pin "58") (pinfunction "MIPI_TX1/RX1_CLKN_58") (pintype "passive+no_connect"))
    )
    (net (code "176") (name "unconnected-(M1-MIPI_TX1{slash}RX1_CLKP-Pad59)") (class "Default")
      (node (ref "M1") (pin "59") (pinfunction "MIPI_TX1/RX1_CLKP_59") (pintype "passive+no_connect"))
    )
    (net (code "177") (name "unconnected-(M1-MIPI_TX1{slash}RX1_D0N-Pad54)") (class "Default")
      (node (ref "M1") (pin "54") (pinfunction "MIPI_TX1/RX1_D0N_54") (pintype "passive+no_connect"))
    )
    (net (code "178") (name "unconnected-(M1-MIPI_TX1{slash}RX1_D0P-Pad55)") (class "Default")
      (node (ref "M1") (pin "55") (pinfunction "MIPI_TX1/RX1_D0P_55") (pintype "passive+no_connect"))
    )
    (net (code "179") (name "unconnected-(M1-MIPI_TX1{slash}RX1_D1N-Pad56)") (class "Default")
      (node (ref "M1") (pin "56") (pinfunction "MIPI_TX1/RX1_D1N_56") (pintype "passive+no_connect"))
    )
    (net (code "180") (name "unconnected-(M1-MIPI_TX1{slash}RX1_D1P-Pad57)") (class "Default")
      (node (ref "M1") (pin "57") (pinfunction "MIPI_TX1/RX1_D1P_57") (pintype "passive+no_connect"))
    )
    (net (code "181") (name "unconnected-(M1-MIPI_TX1{slash}RX1_D2N-Pad60)") (class "Default")
      (node (ref "M1") (pin "60") (pinfunction "MIPI_TX1/RX1_D2N_60") (pintype "passive+no_connect"))
    )
    (net (code "182") (name "unconnected-(M1-MIPI_TX1{slash}RX1_D2P-Pad61)") (class "Default")
      (node (ref "M1") (pin "61") (pinfunction "MIPI_TX1/RX1_D2P_61") (pintype "passive+no_connect"))
    )
    (net (code "183") (name "unconnected-(M1-MIPI_TX1{slash}RX1_D3N-Pad62)") (class "Default")
      (node (ref "M1") (pin "62") (pinfunction "MIPI_TX1/RX1_D3N_62") (pintype "passive+no_connect"))
    )
    (net (code "184") (name "unconnected-(M1-MIPI_TX1{slash}RX1_D3P-Pad63)") (class "Default")
      (node (ref "M1") (pin "63") (pinfunction "MIPI_TX1/RX1_D3P_63") (pintype "passive+no_connect"))
    )
    (net (code "185") (name "unconnected-(M1-TYPEC0_RX1N-Pad97)") (class "Default")
      (node (ref "M1") (pin "97") (pinfunction "TYPEC0_RX1N_97") (pintype "passive+no_connect"))
    )
    (net (code "186") (name "unconnected-(M1-TYPEC0_RX1P-Pad98)") (class "Default")
      (node (ref "M1") (pin "98") (pinfunction "TYPEC0_RX1P_98") (pintype "passive+no_connect"))
    )
    (net (code "187") (name "unconnected-(M1-TYPEC0_RX2N-Pad101)") (class "Default")
      (node (ref "M1") (pin "101") (pinfunction "TYPEC0_RX2N_101") (pintype "passive+no_connect"))
    )
    (net (code "188") (name "unconnected-(M1-TYPEC0_RX2N-Pad102)") (class "Default")
      (node (ref "M1") (pin "102") (pinfunction "TYPEC0_RX2N_102") (pintype "passive+no_connect"))
    )
    (net (code "189") (name "unconnected-(M1-TYPEC0_SBU1-Pad96)") (class "Default")
      (node (ref "M1") (pin "96") (pinfunction "TYPEC0_SBU1_96") (pintype "passive+no_connect"))
    )
    (net (code "190") (name "unconnected-(M1-TYPEC0_SBU1_DC-Pad93)") (class "Default")
      (node (ref "M1") (pin "93") (pinfunction "TYPEC0_SBU1_DC_93") (pintype "passive+no_connect"))
    )
    (net (code "191") (name "unconnected-(M1-TYPEC0_SBU2-Pad95)") (class "Default")
      (node (ref "M1") (pin "95") (pinfunction "TYPEC0_SBU2_95") (pintype "passive+no_connect"))
    )
    (net (code "192") (name "unconnected-(M1-TYPEC0_SBU2_DC-Pad94)") (class "Default")
      (node (ref "M1") (pin "94") (pinfunction "TYPEC0_SBU2_DC_94") (pintype "passive+no_connect"))
    )
    (net (code "193") (name "unconnected-(M1-TYPEC0_TX1N-Pad100)") (class "Default")
      (node (ref "M1") (pin "100") (pinfunction "TYPEC0_TX1N_100") (pintype "passive+no_connect"))
    )
    (net (code "194") (name "unconnected-(M1-TYPEC0_TX1P-Pad99)") (class "Default")
      (node (ref "M1") (pin "99") (pinfunction "TYPEC0_TX1P_99") (pintype "passive+no_connect"))
    )
    (net (code "195") (name "unconnected-(M1-TYPEC0_TX2N-Pad104)") (class "Default")
      (node (ref "M1") (pin "104") (pinfunction "TYPEC0_TX2N_104") (pintype "passive+no_connect"))
    )
    (net (code "196") (name "unconnected-(M1-TYPEC0_TX2P-Pad103)") (class "Default")
      (node (ref "M1") (pin "103") (pinfunction "TYPEC0_TX2P_103") (pintype "passive+no_connect"))
    )
    (net (code "197") (name "unconnected-(M1-USB3_DM-Pad114)") (class "Default")
      (node (ref "M1") (pin "114") (pinfunction "USB3_DM_114") (pintype "passive+no_connect"))
    )
    (net (code "198") (name "unconnected-(M1-USB3_DP-Pad115)") (class "Default")
      (node (ref "M1") (pin "115") (pinfunction "USB3_DP_115") (pintype "passive+no_connect"))
    )
    (net (code "199") (name "unconnected-(M1-USB3_SSRXN-Pad110)") (class "Default")
      (node (ref "M1") (pin "110") (pinfunction "USB3_SSRXN_110") (pintype "passive+no_connect"))
    )
    (net (code "200") (name "unconnected-(M1-USB3_SSRXP-Pad109)") (class "Default")
      (node (ref "M1") (pin "109") (pinfunction "USB3_SSRXP_109") (pintype "passive+no_connect"))
    )
    (net (code "201") (name "unconnected-(M1-USB3_SSTXN-Pad108)") (class "Default")
      (node (ref "M1") (pin "108") (pinfunction "USB3_SSTXN_108") (pintype "passive+no_connect"))
    )
    (net (code "202") (name "unconnected-(M1-USB3_SSTXP-Pad107)") (class "Default")
      (node (ref "M1") (pin "107") (pinfunction "USB3_SSTXP_107") (pintype "passive+no_connect"))
    )
    (net (code "203") (name "unconnected-(M1-VCC_CHAREG_EN-Pad50)") (class "Default")
      (node (ref "M1") (pin "50") (pinfunction "VCC_CHAREG_EN_50") (pintype "passive+no_connect"))
    )
  )
)
